# LPCB220_-_LASER_CHANNEL.net
KiCad netlist of a schematic drawn in Altium Designer
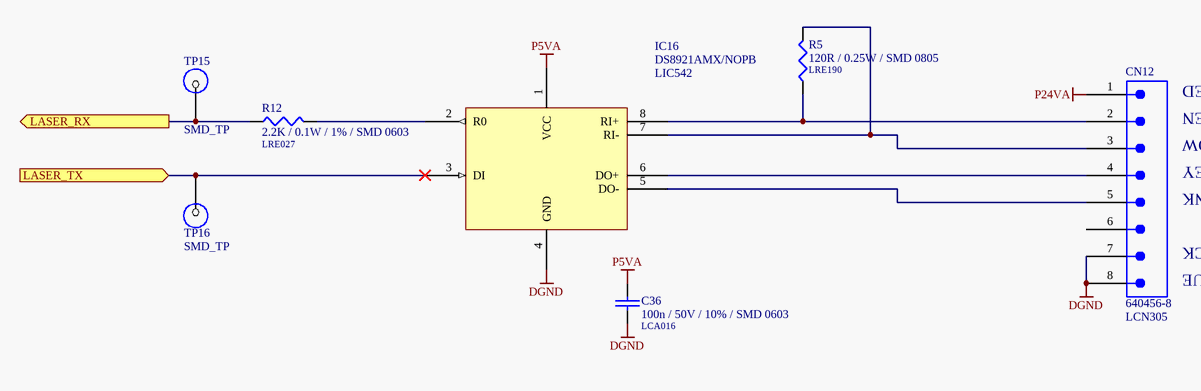
[diagram p0: LPCB220 - LASER CHANNEL.SchDoc]

(export (version "E")
  (design (tool "Eeschema 10.0.6"))
  (components
    (comp (ref "C36")
      (value "100n / 50V / 10% / SMD 0603")
      (footprint "LFP011__CC1608-0603-IPC7351_B")
      (description "Capacitor, Ceramic Chip, 100nF (0.1uF), 50V, 5%, SMD 0603 [LCA016]")
      (fields (field (name "LDL_NUMBER") "LCA016"))
      (libsource (lib "LDL_Capacitors") (part "100n / 50V / 10% / SMD 0603"))
    )
    (comp (ref "CN12")
      (value "640456-8")
      (footprint "640456-8")
      (description "Connector, Male Header, 8 Way")
      (fields (field (name "LDL_NUMBER") "LCN305"))
      (libsource (lib "LDL_Connectors") (part "640456-8"))
    )
    (comp (ref "IC16")
      (value "DS8921AMX/NOPB")
      (footprint "LFP069__R-8G")
      (description "IC, RS422 Tx Rx, SMD SOIC 8")
      (fields (field (name "LDL_NUMBER") "LIC542"))
      (libsource (lib "LDL_Semiconductors") (part "DS8921AMX/NOPB"))
    )
    (comp (ref "R5")
      (value "120R / 0.25W / SMD 0805")
      (footprint "LFP029__CR2012-0805")
      (description "Resistor, Thick Film, 120R, 0.25W, 5%, SMD 0805 [LRE190]")
      (fields (field (name "LDL_NUMBER") "LRE190"))
      (libsource (lib "LDL_Resistors") (part "120R / 0.25W / SMD 0805"))
    )
    (comp (ref "R12")
      (value "2.2K / 0.1W / 1% / SMD 0603")
      (footprint "LFP020__CR1608-0603-IPC7351_B")
      (description "Resistor, Ceramic Chip, 2.2K, 0.1W, 1%, SMD 0603 [LRE027]")
      (fields (field (name "LDL_NUMBER") "LRE027"))
      (libsource (lib "LDL_Resistors") (part "2.2K / 0.1W / 1% / SMD 0603"))
    )
    (comp (ref "TP15")
      (value "SMD_TP")
      (footprint "SMD-TP")
      (description "SMD Test Point")
      (libsource (lib "LDL_Connectors") (part "SMD_TP"))
    )
    (comp (ref "TP16")
      (value "SMD_TP")
      (footprint "SMD-TP")
      (description "SMD Test Point")
      (libsource (lib "LDL_Connectors") (part "SMD_TP"))
    )
  )
  (nets
    (net (code "1") (name "/LASER_RX") (class "Default")
      (node (ref "R12") (pin "1") (pintype "passive"))
      (node (ref "TP15") (pin "1") (pintype "passive"))
    )
    (net (code "2") (name "/LASER_TX") (class "Default")
      (node (ref "IC16") (pin "3") (pinfunction "DI_3") (pintype "input"))
      (node (ref "TP16") (pin "1") (pintype "passive"))
    )
    (net (code "3") (name "DGND") (class "Default")
      (node (ref "C36") (pin "2") (pintype "passive"))
      (node (ref "CN12") (pin "7") (pinfunction "7_7") (pintype "passive"))
      (node (ref "CN12") (pin "8") (pinfunction "8_8") (pintype "passive"))
      (node (ref "IC16") (pin "4") (pinfunction "GND_4") (pintype "power_in"))
    )
    (net (code "4") (name "Net-(IC16-DO+)") (class "Default")
      (node (ref "CN12") (pin "4") (pinfunction "4_4") (pintype "passive"))
      (node (ref "IC16") (pin "6") (pinfunction "DO+_6") (pintype "passive"))
    )
    (net (code "5") (name "Net-(IC16-DO-)") (class "Default")
      (node (ref "CN12") (pin "5") (pinfunction "5_5") (pintype "passive"))
      (node (ref "IC16") (pin "5") (pinfunction "DO-_5") (pintype "passive"))
    )
    (net (code "6") (name "Net-(IC16-R0)") (class "Default")
      (node (ref "IC16") (pin "2") (pinfunction "R0_2") (pintype "output"))
      (node (ref "R12") (pin "2") (pintype "passive"))
    )
    (net (code "7") (name "Net-(IC16-RI+)") (class "Default")
      (node (ref "CN12") (pin "2") (pinfunction "2_2") (pintype "passive"))
      (node (ref "IC16") (pin "8") (pinfunction "RI+_8") (pintype "passive"))
      (node (ref "R5") (pin "1") (pintype "passive"))
    )
    (net (code "8") (name "Net-(IC16-RI-)") (class "Default")
      (node (ref "CN12") (pin "3") (pinfunction "3_3") (pintype "passive"))
      (node (ref "IC16") (pin "7") (pinfunction "RI-_7") (pintype "passive"))
      (node (ref "R5") (pin "2") (pintype "passive"))
    )
    (net (code "9") (name "P5VA") (class "Default")
      (node (ref "C36") (pin "1") (pintype "passive"))
      (node (ref "IC16") (pin "1") (pinfunction "VCC_1") (pintype "power_in"))
    )
    (net (code "10") (name "P24VA") (class "Default")
      (node (ref "CN12") (pin "1") (pinfunction "1_1") (pintype "passive"))
    )
    (net (code "11") (name "unconnected-(CN12-Pad6)") (class "Default")
      (node (ref "CN12") (pin "6") (pinfunction "6_6") (pintype "passive"))
    )
  )
)
